# Sheet1.net
KiCad netlist of a schematic drawn in Altium Designer
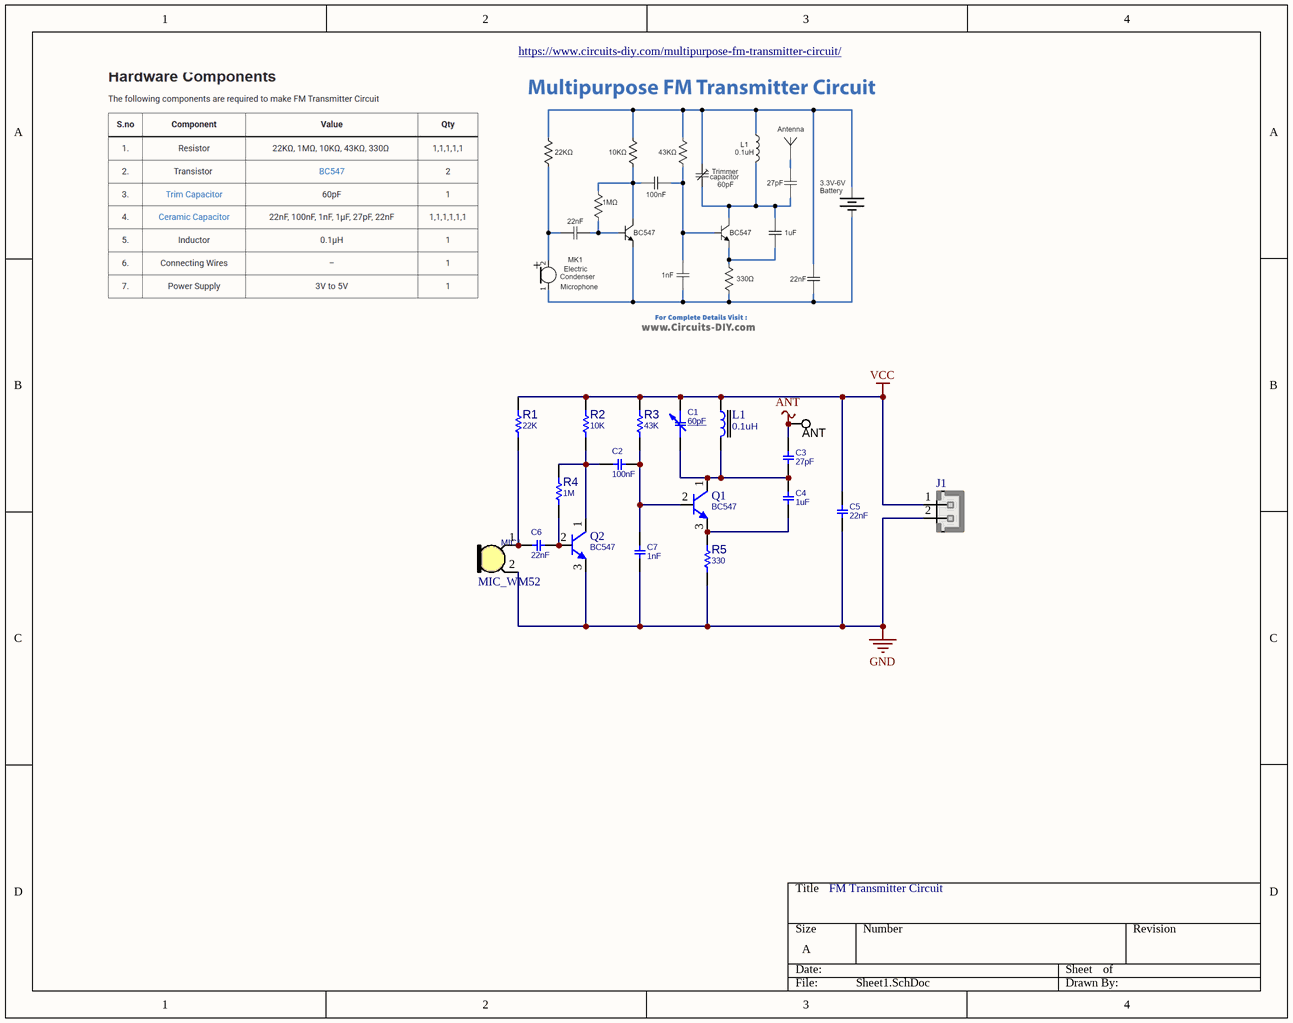
[diagram p0: Sheet1.SchDoc]

(export (version "E")
  (design (tool "Eeschema 10.0.6"))
  (components
    (comp (ref "ANT")
      (value "TESTPOINT_PROBE")
      (footprint "TPTHD_A")
      (description "TEST POINT")
      (fields (field (name "MANF") "MANF") (field (name "MANF_P#") "MANF_P#"))
      (libsource (lib "test-tp_jumper") (part "TESTPOINT_PROBE"))
    )
    (comp (ref "C1")
      (value "60pF")
      (footprint "CTRM_6X6")
      (description "CAP, THD, TRIMMER")
      (fields (field (name "MANF_P#") "MANF_PART#") (field (name "MANF") "MANF"))
      (libsource (lib "passive_thd") (part "CAP_THD_TRIMMER"))
    )
    (comp (ref "C2")
      (value "100nF")
      (footprint "C_CER_D5")
      (description "CAP, THD, CER MULTI LAYER,")
      (fields (field (name "MANF_P#") "MANF_PART#") (field (name "MANF") "MANF"))
      (libsource (lib "passive_thd") (part "CAP_THD_CER"))
    )
    (comp (ref "C3")
      (value "27pF")
      (footprint "C_CER_D5")
      (description "CAP, THD, CER MULTI LAYER,")
      (fields (field (name "MANF_P#") "MANF_PART#") (field (name "MANF") "MANF"))
      (libsource (lib "passive_thd") (part "CAP_THD_CER"))
    )
    (comp (ref "C4")
      (value "1uF")
      (footprint "C_CER_D5")
      (description "CAP, THD, CER MULTI LAYER,")
      (fields (field (name "MANF_P#") "MANF_PART#") (field (name "MANF") "MANF"))
      (libsource (lib "passive_thd") (part "CAP_THD_CER"))
    )
    (comp (ref "C5")
      (value "22nF")
      (footprint "C_CER_D5")
      (description "CAP, THD, CER MULTI LAYER,")
      (fields (field (name "MANF_P#") "MANF_PART#") (field (name "MANF") "MANF"))
      (libsource (lib "passive_thd") (part "CAP_THD_CER"))
    )
    (comp (ref "C6")
      (value "22nF")
      (footprint "C_CER_D5")
      (description "CAP, THD, CER MULTI LAYER,")
      (fields (field (name "MANF_P#") "MANF_PART#") (field (name "MANF") "MANF"))
      (libsource (lib "passive_thd") (part "CAP_THD_CER"))
    )
    (comp (ref "C7")
      (value "1nF")
      (footprint "C_CER_D5")
      (description "CAP, THD, CER MULTI LAYER,")
      (fields (field (name "MANF_P#") "MANF_PART#") (field (name "MANF") "MANF"))
      (libsource (lib "passive_thd") (part "CAP_THD_CER"))
    )
    (comp (ref "J1")
      (value "HHDR_2")
      (footprint "XH_2")
      (description "JST-XH pitch: 2.5mm")
      (libsource (lib "conn_wire2board") (part "XH_2"))
    )
    (comp (ref "L1")
      (value "0.1uH")
      (footprint "LT_AX025")
      (description "INDUCTOR, THD")
      (libsource (lib "passive_thd") (part "IND_THD"))
    )
    (comp (ref "MIC1")
      (value "MIC_WM52")
      (footprint "MIC_C6")
      (description "MICROPHONE OMNI")
      (fields (field (name "MANF_P#") "WM52BM"))
      (libsource (lib "audio_mic_spk") (part "MIC_WM-52"))
    )
    (comp (ref "Q1")
      (value "BC547")
      (footprint "TO92_3")
      (description "BJT, NPN, 45v, 0.1A, THD, TO92")
      (fields (field (name "MANF") "FAIRCHILD"))
      (libsource (lib "transistor_bjt") (part "NPN_BC547_TO92"))
    )
    (comp (ref "Q2")
      (value "BC547")
      (footprint "TO92_3")
      (description "BJT, NPN, 45v, 0.1A, THD, TO92")
      (fields (field (name "MANF") "FAIRCHILD"))
      (libsource (lib "transistor_bjt") (part "NPN_BC547_TO92"))
    )
    (comp (ref "R1")
      (value "22K")
      (footprint "R025W_AX04")
      (description "RESISTOR, THD")
      (fields (field (name "MANF_P#") "RK73H1ETTP4701F") (field (name "MANF") "KOA SPEER"))
      (libsource (lib "passive") (part "RES_THD"))
    )
    (comp (ref "R2")
      (value "10K")
      (footprint "R025W_AX04")
      (description "RESISTOR, THD")
      (fields (field (name "MANF_P#") "RK73H1ETTP4701F") (field (name "MANF") "KOA SPEER"))
      (libsource (lib "passive") (part "RES_THD"))
    )
    (comp (ref "R3")
      (value "43K")
      (footprint "R025W_AX04")
      (description "RESISTOR, THD")
      (fields (field (name "MANF_P#") "RK73H1ETTP4701F") (field (name "MANF") "KOA SPEER"))
      (libsource (lib "passive") (part "RES_THD"))
    )
    (comp (ref "R4")
      (value "1M")
      (footprint "R025W_AX04")
      (description "RESISTOR, THD")
      (fields (field (name "MANF_P#") "RK73H1ETTP4701F") (field (name "MANF") "KOA SPEER"))
      (libsource (lib "passive") (part "RES_THD"))
    )
    (comp (ref "R5")
      (value "330")
      (footprint "R025W_AX04")
      (description "RESISTOR, THD")
      (fields (field (name "MANF_P#") "RK73H1ETTP4701F") (field (name "MANF") "KOA SPEER"))
      (libsource (lib "passive") (part "RES_THD"))
    )
  )
  (nets
    (net (code "1") (name "ANT") (class "Default")
      (node (ref "ANT") (pin "1") (pinfunction "1_1") (pintype "passive"))
      (node (ref "C3") (pin "2") (pinfunction "2_2") (pintype "passive"))
    )
    (net (code "2") (name "GND") (class "Default")
      (node (ref "C5") (pin "1") (pinfunction "1_1") (pintype "passive"))
      (node (ref "C7") (pin "1") (pinfunction "1_1") (pintype "passive"))
      (node (ref "J1") (pin "2") (pinfunction "2_2") (pintype "passive"))
      (node (ref "MIC1") (pin "2") (pinfunction "GND_2") (pintype "passive"))
      (node (ref "Q2") (pin "3") (pinfunction "E_3") (pintype "passive"))
      (node (ref "R5") (pin "1") (pinfunction "1_1") (pintype "passive"))
    )
    (net (code "3") (name "Net-(MIC1-OUT)") (class "Default")
      (node (ref "C6") (pin "2") (pinfunction "2_2") (pintype "passive"))
      (node (ref "MIC1") (pin "1") (pinfunction "OUT_1") (pintype "passive"))
      (node (ref "R1") (pin "1") (pinfunction "1_1") (pintype "passive"))
    )
    (net (code "4") (name "Net-(Q1-B)") (class "Default")
      (node (ref "C2") (pin "1") (pinfunction "1_1") (pintype "passive"))
      (node (ref "C7") (pin "2") (pinfunction "2_2") (pintype "passive"))
      (node (ref "Q1") (pin "2") (pinfunction "B_2") (pintype "passive"))
      (node (ref "R3") (pin "1") (pinfunction "1_1") (pintype "passive"))
    )
    (net (code "5") (name "Net-(Q1-C)") (class "Default")
      (node (ref "C1") (pin "1") (pinfunction "1_1") (pintype "passive"))
      (node (ref "C3") (pin "1") (pinfunction "1_1") (pintype "passive"))
      (node (ref "C4") (pin "2") (pinfunction "2_2") (pintype "passive"))
      (node (ref "L1") (pin "2") (pinfunction "2_2") (pintype "passive"))
      (node (ref "Q1") (pin "1") (pinfunction "C_1") (pintype "passive"))
    )
    (net (code "6") (name "Net-(Q1-E)") (class "Default")
      (node (ref "C4") (pin "1") (pinfunction "1_1") (pintype "passive"))
      (node (ref "Q1") (pin "3") (pinfunction "E_3") (pintype "passive"))
      (node (ref "R5") (pin "2") (pinfunction "2_2") (pintype "passive"))
    )
    (net (code "7") (name "Net-(Q2-B)") (class "Default")
      (node (ref "C6") (pin "1") (pinfunction "1_1") (pintype "passive"))
      (node (ref "Q2") (pin "2") (pinfunction "B_2") (pintype "passive"))
      (node (ref "R4") (pin "1") (pinfunction "1_1") (pintype "passive"))
    )
    (net (code "8") (name "Net-(Q2-C)") (class "Default")
      (node (ref "C2") (pin "2") (pinfunction "2_2") (pintype "passive"))
      (node (ref "Q2") (pin "1") (pinfunction "C_1") (pintype "passive"))
      (node (ref "R2") (pin "1") (pinfunction "1_1") (pintype "passive"))
      (node (ref "R4") (pin "2") (pinfunction "2_2") (pintype "passive"))
    )
    (net (code "9") (name "VCC") (class "Default")
      (node (ref "C1") (pin "2") (pinfunction "2_2") (pintype "passive"))
      (node (ref "C5") (pin "2") (pinfunction "2_2") (pintype "passive"))
      (node (ref "J1") (pin "1") (pinfunction "1_1") (pintype "passive"))
      (node (ref "L1") (pin "1") (pinfunction "1_1") (pintype "passive"))
      (node (ref "R1") (pin "2") (pinfunction "2_2") (pintype "passive"))
      (node (ref "R2") (pin "2") (pinfunction "2_2") (pintype "passive"))
      (node (ref "R3") (pin "2") (pinfunction "2_2") (pintype "passive"))
    )
  )
)
